# Ethernet_Interface.net
KiCad netlist of a schematic drawn in Altium Designer
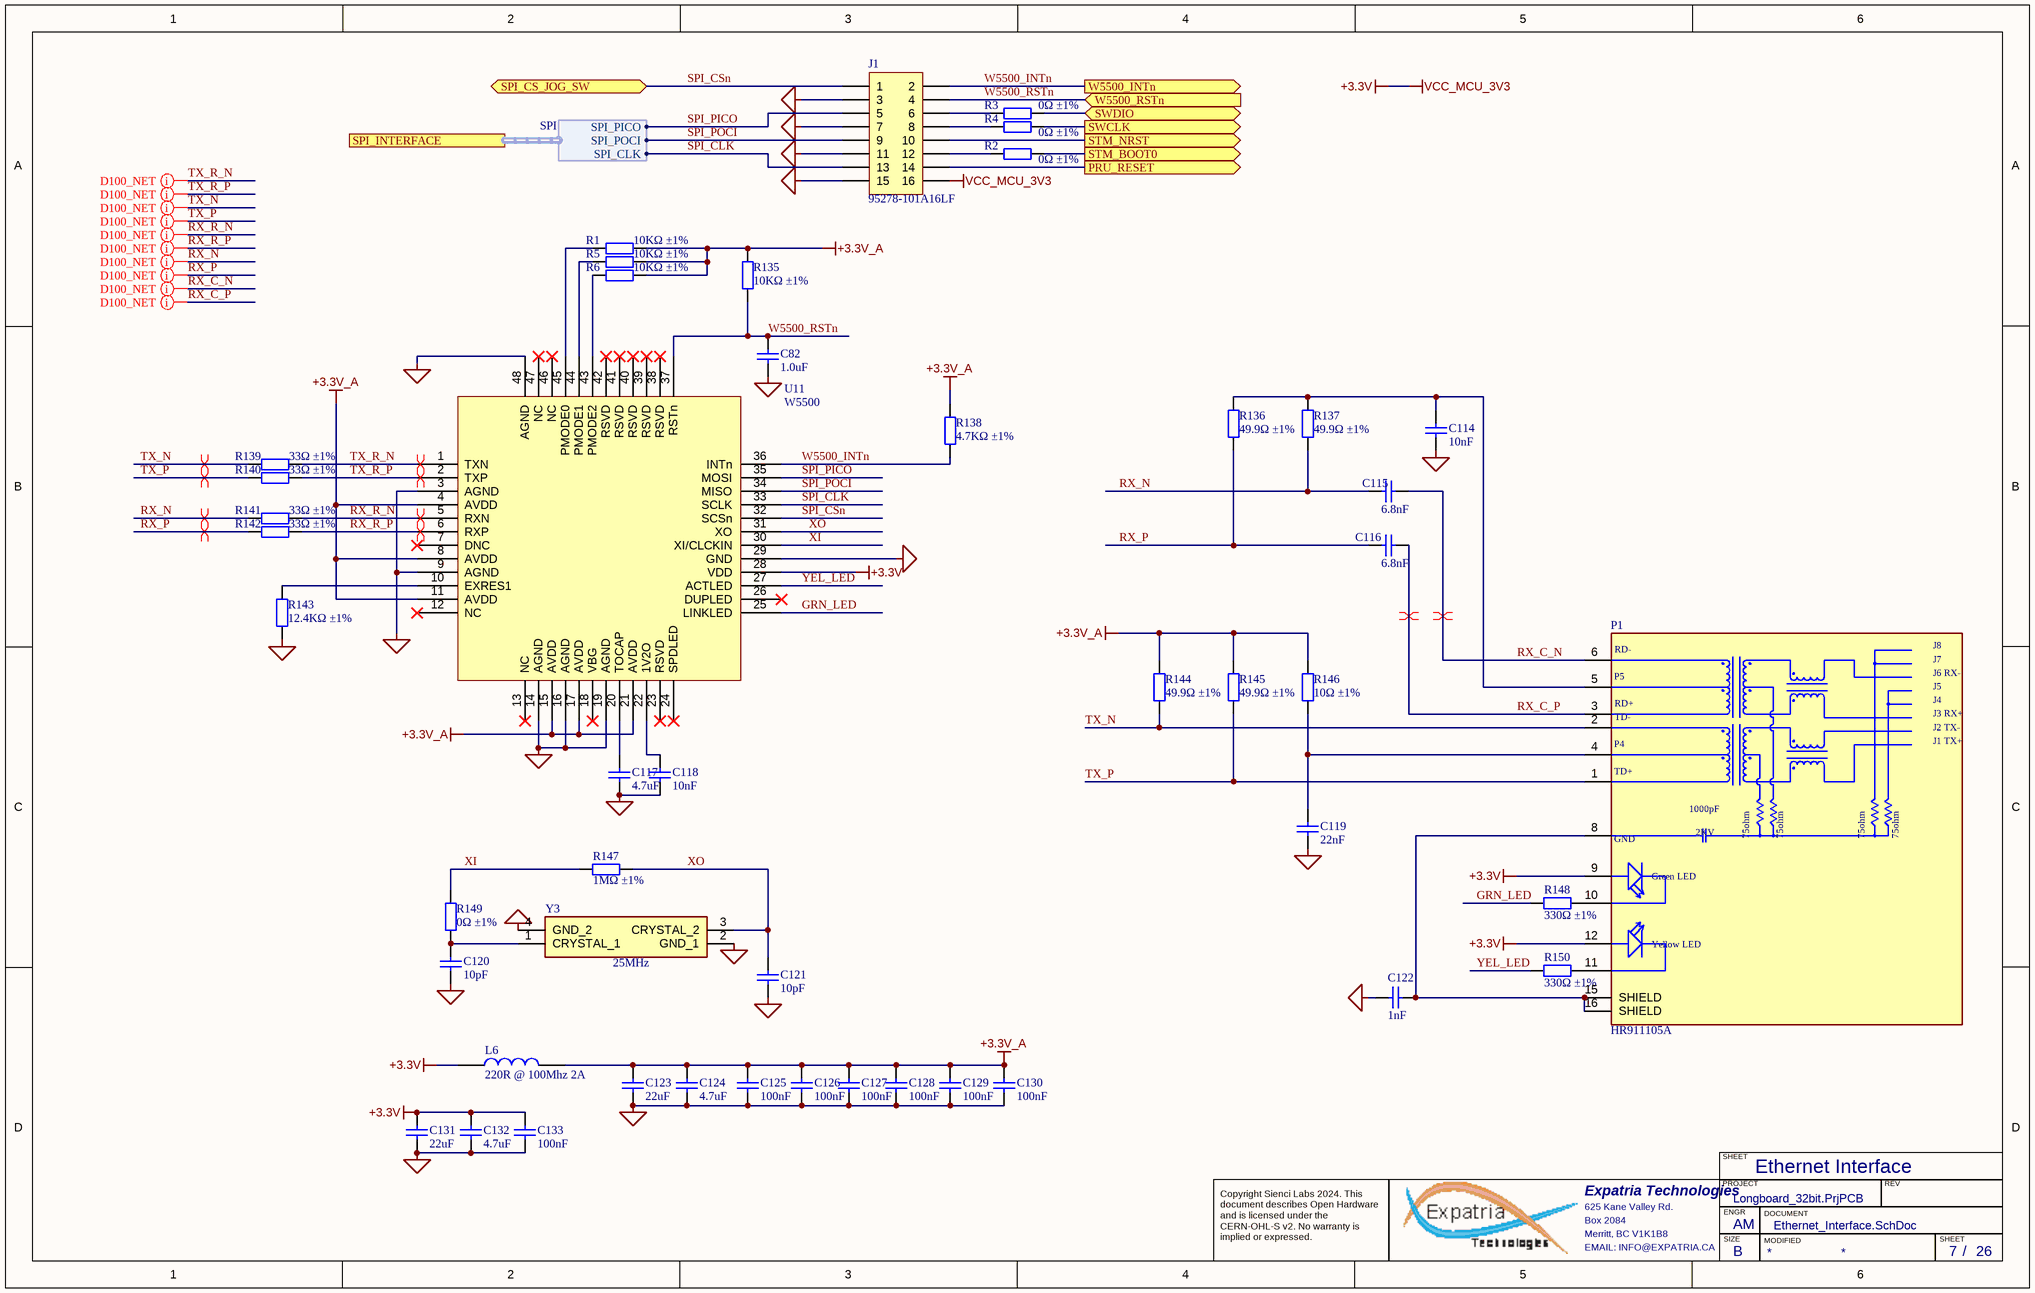
[diagram p0: Ethernet_Interface.SchDoc]

(export (version "E")
  (design (tool "Eeschema 10.0.6"))
  (components
    (comp (ref "C82")
      (value "1.0uF")
      (footprint "0402_C")
      (description "Chip capacitor")
      (fields (field (name "MANUFACTURER") "Samsung Electro-Mechanics") (field (name "TOLERANCE") "10%"))
      (libsource (lib "Cap") (part "0402 1.0uF (105) 10% 25V"))
    )
    (comp (ref "C114")
      (value "10nF")
      (footprint "0402_C")
      (description "Chip capacitors")
      (fields
        (field (name "MANUFACTURER") "Samsung Electro-Mechanics")
        (field (name "MANUFACTURER PART NUMBER") "CL05B103KB5NNNC")
      )
      (libsource (lib "Cap") (part "0402 10nF (103) 10% 50V"))
    )
    (comp (ref "C115")
      (value "6.8nF")
      (footprint "0402_C")
      (description "Chip capacitors")
      (fields
        (field (name "MANUFACTURER") "Guangdong Fenghua Advanced Tech")
        (field (name "MANUFACTURER PART NUMBER") "0402B682K500NT")
      )
      (libsource (lib "Cap") (part "0402 6.8nF (682) 10% 50V"))
    )
    (comp (ref "C116")
      (value "6.8nF")
      (footprint "0402_C")
      (description "Chip capacitors")
      (fields
        (field (name "MANUFACTURER") "Guangdong Fenghua Advanced Tech")
        (field (name "MANUFACTURER PART NUMBER") "0402B682K500NT")
      )
      (libsource (lib "Cap") (part "0402 6.8nF (682) 10% 50V"))
    )
    (comp (ref "C117")
      (value "4.7uF")
      (footprint "0402_C")
      (description "Chip capacitor")
      (fields
        (field (name "MANUFACTURER") "Samsung Electro-Mechanics")
        (field (name "MANUFACTURER PART NUMBER") "CL05A475MP5NRNC")
      )
      (libsource (lib "Cap") (part "0402 4.7uF (475) 20% 10V"))
    )
    (comp (ref "C118")
      (value "10nF")
      (footprint "0402_C")
      (description "Chip capacitors")
      (fields
        (field (name "MANUFACTURER") "Samsung Electro-Mechanics")
        (field (name "MANUFACTURER PART NUMBER") "CL05B103KB5NNNC")
      )
      (libsource (lib "Cap") (part "0402 10nF (103) 10% 50V"))
    )
    (comp (ref "C119")
      (value "22nF")
      (footprint "0402_C")
      (description "Chip capacitors")
      (fields
        (field (name "MANUFACTURER") "Guangdong Fenghua Advanced Tech")
        (field (name "MANUFACTURER PART NUMBER") "0402B223K500NT")
      )
      (libsource (lib "Cap") (part "0402 22nF (223) 10% 50V"))
    )
    (comp (ref "C120")
      (value "10pF")
      (footprint "0402_C")
      (description "Chip capacitors")
      (fields
        (field (name "MANUFACTURER") "Samsung Electro-Mechanics")
        (field (name "MANUFACTURER PART NUMBER") "CL05C100JB5NNNC")
      )
      (libsource (lib "Cap") (part "0402 10pF (100) 5% 50V"))
    )
    (comp (ref "C121")
      (value "10pF")
      (footprint "0402_C")
      (description "Chip capacitors")
      (fields
        (field (name "MANUFACTURER") "Samsung Electro-Mechanics")
        (field (name "MANUFACTURER PART NUMBER") "CL05C100JB5NNNC")
      )
      (libsource (lib "Cap") (part "0402 10pF (100) 5% 50V"))
    )
    (comp (ref "C122")
      (value "1nF")
      (footprint "1206_C")
      (description "Chip capacitors")
      (fields
        (field (name "MANUFACTURER") "Samsung Electro-Mechanics")
        (field (name "MANUFACTURER PART NUMBER") "CL31B102KGFNNNE")
      )
      (libsource (lib "Cap") (part "1206 1nF (102) 10% 500V"))
    )
    (comp (ref "C123")
      (value "22uF")
      (footprint "0805_C")
      (description "25V 22uF X5R ±20% 0805 Multilayer Ceramic Capacitors MLCC - SMD/SMT ROHS")
      (fields (field (name "MANUFACTURER") "Samsung Electro-Mechanics") (field (name "TOLERANCE") "20%"))
      (libsource (lib "Sienci_Labs") (part "0805 22uF (226) 20% 25V"))
    )
    (comp (ref "C124")
      (value "4.7uF")
      (footprint "0603_C")
      (description "16V 4.7uF X5R ±10% 0603 Multilayer Ceramic Capacitors MLCC - SMD/SMT ROHS")
      (fields (field (name "MANUFACTURER") "Samsung Electro-Mechanics") (field (name "TOLERANCE") "10%"))
      (libsource (lib "Sienci_Labs") (part "0603 4.7uF (475) 10% 16V"))
    )
    (comp (ref "C125")
      (value "100nF")
      (footprint "0402_C")
      (description "16V 100nF X7R ±10% 0402 Multilayer Ceramic Capacitors MLCC - SMD/SMT ROHS")
      (fields (field (name "MANUFACTURER") "Samsung Electro-Mechanics") (field (name "TOLERANCE") "10%"))
      (libsource (lib "Sienci_Labs") (part "0402 100nF (104) 10% 16V"))
    )
    (comp (ref "C126")
      (value "100nF")
      (footprint "0402_C")
      (description "16V 100nF X7R ±10% 0402 Multilayer Ceramic Capacitors MLCC - SMD/SMT ROHS")
      (fields (field (name "MANUFACTURER") "Samsung Electro-Mechanics") (field (name "TOLERANCE") "10%"))
      (libsource (lib "Sienci_Labs") (part "0402 100nF (104) 10% 16V"))
    )
    (comp (ref "C127")
      (value "100nF")
      (footprint "0402_C")
      (description "16V 100nF X7R ±10% 0402 Multilayer Ceramic Capacitors MLCC - SMD/SMT ROHS")
      (fields (field (name "MANUFACTURER") "Samsung Electro-Mechanics") (field (name "TOLERANCE") "10%"))
      (libsource (lib "Sienci_Labs") (part "0402 100nF (104) 10% 16V"))
    )
    (comp (ref "C128")
      (value "100nF")
      (footprint "0402_C")
      (description "16V 100nF X7R ±10% 0402 Multilayer Ceramic Capacitors MLCC - SMD/SMT ROHS")
      (fields (field (name "MANUFACTURER") "Samsung Electro-Mechanics") (field (name "TOLERANCE") "10%"))
      (libsource (lib "Sienci_Labs") (part "0402 100nF (104) 10% 16V"))
    )
    (comp (ref "C129")
      (value "100nF")
      (footprint "0402_C")
      (description "16V 100nF X7R ±10% 0402 Multilayer Ceramic Capacitors MLCC - SMD/SMT ROHS")
      (fields (field (name "MANUFACTURER") "Samsung Electro-Mechanics") (field (name "TOLERANCE") "10%"))
      (libsource (lib "Sienci_Labs") (part "0402 100nF (104) 10% 16V"))
    )
    (comp (ref "C130")
      (value "100nF")
      (footprint "0402_C")
      (description "16V 100nF X7R ±10% 0402 Multilayer Ceramic Capacitors MLCC - SMD/SMT ROHS")
      (fields (field (name "MANUFACTURER") "Samsung Electro-Mechanics") (field (name "TOLERANCE") "10%"))
      (libsource (lib "Sienci_Labs") (part "0402 100nF (104) 10% 16V"))
    )
    (comp (ref "C131")
      (value "22uF")
      (footprint "0805_C")
      (description "25V 22uF X5R ±20% 0805 Multilayer Ceramic Capacitors MLCC - SMD/SMT ROHS")
      (fields (field (name "MANUFACTURER") "Samsung Electro-Mechanics") (field (name "TOLERANCE") "20%"))
      (libsource (lib "Sienci_Labs") (part "0805 22uF (226) 20% 25V"))
    )
    (comp (ref "C132")
      (value "4.7uF")
      (footprint "0603_C")
      (description "16V 4.7uF X5R ±10% 0603 Multilayer Ceramic Capacitors MLCC - SMD/SMT ROHS")
      (fields (field (name "MANUFACTURER") "Samsung Electro-Mechanics") (field (name "TOLERANCE") "10%"))
      (libsource (lib "Sienci_Labs") (part "0603 4.7uF (475) 10% 16V"))
    )
    (comp (ref "C133")
      (value "100nF")
      (footprint "0402_C")
      (description "16V 100nF X7R ±10% 0402 Multilayer Ceramic Capacitors MLCC - SMD/SMT ROHS")
      (fields (field (name "MANUFACTURER") "Samsung Electro-Mechanics") (field (name "TOLERANCE") "10%"))
      (libsource (lib "Sienci_Labs") (part "0402 100nF (104) 10% 16V"))
    )
    (comp (ref "J1")
      (value "95278-101A16LF")
      (footprint "95278101A16LF")
      (description "Conn Unshrouded Header HDR 16 POS 2.54mm Solder ST Top Entry SMD BergStik® T/R")
      (fields (field (name "MANUFACTURER") "Amphenol ICC / FCI"))
      (libsource (lib "Sienci_Labs") (part "95278-101A16LF"))
    )
    (comp (ref "L6")
      (value "220R @ 100Mhz 2A")
      (footprint "0805_R")
      (description "150mΩ ±25% 220Ω@100MHz 0805 Ferrite Beads ROHS")
      (fields
        (field (name "MANUFACTURER PART NUMBER") "CBW201209U221T")
        (field (name "MANUFACTURER") "FH (Guangdong Fenghua Advanced Tech)")
      )
      (libsource (lib "Sienci_Labs") (part "CBW201209U221T"))
    )
    (comp (ref "P1")
      (value "HR911105A")
      (footprint "HANRUN_HR911105A")
      (description "HR911105A Ethernet Interface Arduino Platform Evaluation Expansion Board")
      (fields (field (name "MANUFACTURER") "DFRobot"))
      (libsource (lib "Sienci_Labs") (part "HR911105A"))
    )
    (comp (ref "R1")
      (value "10KΩ ±1%")
      (footprint "0402_R")
      (description "Chip resistor")
      (fields
        (field (name "MANUFACTURER") "Uniroyal Elec")
        (field (name "MANUFACTURER PART NUMBER") "0402WGF1002TCE")
      )
      (libsource (lib "RES") (part "0402 10K (1002) 1%"))
    )
    (comp (ref "R2")
      (value "0Ω ±1%")
      (footprint "0603_R")
      (description "Chip resistor")
      (fields
        (field (name "MANUFACTURER") "Uniroyal Elec")
        (field (name "MANUFACTURER PART NUMBER") "0603WAF0000T5E")
      )
      (libsource (lib "RES") (part "0603 0R (0R0) 1%"))
    )
    (comp (ref "R3")
      (value "0Ω ±1%")
      (footprint "0603_R")
      (description "Chip resistor")
      (fields
        (field (name "MANUFACTURER") "Uniroyal Elec")
        (field (name "MANUFACTURER PART NUMBER") "0603WAF0000T5E")
      )
      (libsource (lib "RES") (part "0603 0R (0R0) 1%"))
    )
    (comp (ref "R4")
      (value "0Ω ±1%")
      (footprint "0603_R")
      (description "Chip resistor")
      (fields
        (field (name "MANUFACTURER") "Uniroyal Elec")
        (field (name "MANUFACTURER PART NUMBER") "0603WAF0000T5E")
      )
      (libsource (lib "RES") (part "0603 0R (0R0) 1%"))
    )
    (comp (ref "R5")
      (value "10KΩ ±1%")
      (footprint "0402_R")
      (description "Chip resistor")
      (fields
        (field (name "MANUFACTURER") "Uniroyal Elec")
        (field (name "MANUFACTURER PART NUMBER") "0402WGF1002TCE")
      )
      (libsource (lib "RES") (part "0402 10K (1002) 1%"))
    )
    (comp (ref "R6")
      (value "10KΩ ±1%")
      (footprint "0402_R")
      (description "Chip resistor")
      (fields
        (field (name "MANUFACTURER") "Uniroyal Elec")
        (field (name "MANUFACTURER PART NUMBER") "0402WGF1002TCE")
      )
      (libsource (lib "RES") (part "0402 10K (1002) 1%"))
    )
    (comp (ref "R135")
      (value "10KΩ ±1%")
      (footprint "0402_R")
      (description "Chip resistor")
      (fields
        (field (name "MANUFACTURER") "Uniroyal Elec")
        (field (name "MANUFACTURER PART NUMBER") "0402WGF1002TCE")
      )
      (libsource (lib "") (part "0402 10K (1002) 1%_1"))
    )
    (comp (ref "R136")
      (value "49.9Ω ±1%")
      (footprint "0402_R")
      (description "Chip resistor")
      (fields
        (field (name "MANUFACTURER") "Uniroyal Elec")
        (field (name "MANUFACTURER PART NUMBER") "0402WGF499JTCE")
      )
      (libsource (lib "RES") (part "0402 49.9R (49R9) 1%"))
    )
    (comp (ref "R137")
      (value "49.9Ω ±1%")
      (footprint "0402_R")
      (description "Chip resistor")
      (fields
        (field (name "MANUFACTURER") "Uniroyal Elec")
        (field (name "MANUFACTURER PART NUMBER") "0402WGF499JTCE")
      )
      (libsource (lib "RES") (part "0402 49.9R (49R9) 1%"))
    )
    (comp (ref "R138")
      (value "4.7KΩ ±1%")
      (footprint "0402_R")
      (description "Chip resistor")
      (fields
        (field (name "MANUFACTURER") "Uniroyal Elec")
        (field (name "MANUFACTURER PART NUMBER") "0402WGF4701TCE")
      )
      (libsource (lib "RES") (part "0402 4.7K (4701) 1%"))
    )
    (comp (ref "R139")
      (value "33Ω ±1%")
      (footprint "0402_R")
      (description "Chip resistor")
      (fields
        (field (name "MANUFACTURER") "Uniroyal Elec")
        (field (name "MANUFACTURER PART NUMBER") "0402WGF330JTCE")
      )
      (libsource (lib "RES") (part "0402 33R (33R0) 1%"))
    )
    (comp (ref "R140")
      (value "33Ω ±1%")
      (footprint "0402_R")
      (description "Chip resistor")
      (fields
        (field (name "MANUFACTURER") "Uniroyal Elec")
        (field (name "MANUFACTURER PART NUMBER") "0402WGF330JTCE")
      )
      (libsource (lib "RES") (part "0402 33R (33R0) 1%"))
    )
    (comp (ref "R141")
      (value "33Ω ±1%")
      (footprint "0402_R")
      (description "Chip resistor")
      (fields
        (field (name "MANUFACTURER") "Uniroyal Elec")
        (field (name "MANUFACTURER PART NUMBER") "0402WGF330JTCE")
      )
      (libsource (lib "RES") (part "0402 33R (33R0) 1%"))
    )
    (comp (ref "R142")
      (value "33Ω ±1%")
      (footprint "0402_R")
      (description "Chip resistor")
      (fields
        (field (name "MANUFACTURER") "Uniroyal Elec")
        (field (name "MANUFACTURER PART NUMBER") "0402WGF330JTCE")
      )
      (libsource (lib "RES") (part "0402 33R (33R0) 1%"))
    )
    (comp (ref "R143")
      (value "12.4KΩ ±1%")
      (footprint "0603_R")
      (description "Chip resistor")
      (fields
        (field (name "MANUFACTURER") "Uniroyal Elec")
        (field (name "MANUFACTURER PART NUMBER") "0603WAF1242T5E")
      )
      (libsource (lib "RES") (part "0603 10K (1002) 1%"))
    )
    (comp (ref "R144")
      (value "49.9Ω ±1%")
      (footprint "0402_R")
      (description "Chip resistor")
      (fields
        (field (name "MANUFACTURER") "Uniroyal Elec")
        (field (name "MANUFACTURER PART NUMBER") "0402WGF499JTCE")
      )
      (libsource (lib "RES") (part "0402 49.9R (49R9) 1%"))
    )
    (comp (ref "R145")
      (value "49.9Ω ±1%")
      (footprint "0402_R")
      (description "Chip resistor")
      (fields
        (field (name "MANUFACTURER") "Uniroyal Elec")
        (field (name "MANUFACTURER PART NUMBER") "0402WGF499JTCE")
      )
      (libsource (lib "RES") (part "0402 49.9R (49R9) 1%"))
    )
    (comp (ref "R146")
      (value "10Ω ±1%")
      (footprint "0402_R")
      (description "Chip resistor")
      (fields
        (field (name "MANUFACTURER") "Uniroyal Elec")
        (field (name "MANUFACTURER PART NUMBER") "0402WGF100JTCE")
      )
      (libsource (lib "RES") (part "0402 10R (10R0) 1%"))
    )
    (comp (ref "R147")
      (value "1MΩ ±1%")
      (footprint "0402_R")
      (description "Chip resistor")
      (fields
        (field (name "MANUFACTURER") "Uniroyal Elec")
        (field (name "MANUFACTURER PART NUMBER") "0402WGF1004TCE")
      )
      (libsource (lib "RES") (part "0402 1M (1004) 1%"))
    )
    (comp (ref "R148")
      (value "330Ω ±1%")
      (footprint "0402_R")
      (description "Chip resistor")
      (fields
        (field (name "MANUFACTURER") "Uniroyal Elec")
        (field (name "MANUFACTURER PART NUMBER") "0402WGF3300TCE")
      )
      (libsource (lib "RES") (part "0402 330R (3300) 1%"))
    )
    (comp (ref "R149")
      (value "0Ω ±1%")
      (footprint "0402_R")
      (description "Chip resistor")
      (fields
        (field (name "MANUFACTURER") "Uniroyal Elec")
        (field (name "MANUFACTURER PART NUMBER") "0402WGF0000TCE")
      )
      (libsource (lib "RES") (part "0402 0R (0R0) 1%"))
    )
    (comp (ref "R150")
      (value "330Ω ±1%")
      (footprint "0402_R")
      (description "Chip resistor")
      (fields
        (field (name "MANUFACTURER") "Uniroyal Elec")
        (field (name "MANUFACTURER PART NUMBER") "0402WGF3300TCE")
      )
      (libsource (lib "RES") (part "0402 330R (3300) 1%"))
    )
    (comp (ref "U11")
      (value "W5500")
      (footprint "LQFP-48_7x7x05P")
      (description "Ethernet Controllers 2.97V ~ 3.63V 10/100 Base-T/TX PHY SPI LQFP-48_7x7x05P Ethernet ICs ROHS")
      (fields (field (name "MANUFACTURER") "WIZNET"))
      (libsource (lib "Sienci_Labs") (part "W5500_[C32843]"))
    )
    (comp (ref "Y3")
      (value "25MHz")
      (footprint "YSX321SL")
      (description "25MHz SMD Crystal Resonator 20pF ±10ppm ±30ppm -40℃~+85℃ SMD3225-4P Crystals ROHS")
      (fields
        (field (name "MANUFACTURER") "Yangxing Tech")
        (field (name "MANUFACTURER PART NUMBER") "X322525MSB4SI")
      )
      (libsource (lib "Sienci_Labs") (part "X322525MSB4SI"))
    )
  )
  (nets
    (net (code "2") (name "+3.3V") (class "Default")
      (node (ref "C131") (pin "2") (pinfunction "2_2") (pintype "passive"))
      (node (ref "C132") (pin "2") (pinfunction "2_2") (pintype "passive"))
      (node (ref "C133") (pin "2") (pinfunction "2_2") (pintype "passive"))
      (node (ref "J1") (pin "16") (pinfunction "16_16") (pintype "passive"))
      (node (ref "L6") (pin "1") (pinfunction "1_1") (pintype "passive"))
      (node (ref "P1") (pin "12") (pinfunction "YA_12") (pintype "passive"))
      (node (ref "P1") (pin "9") (pinfunction "GA_9") (pintype "passive"))
      (node (ref "U11") (pin "28") (pinfunction "VDD_28") (pintype "passive"))
    )
    (net (code "3") (name "+3.3V_A") (class "Default")
      (node (ref "C123") (pin "2") (pinfunction "2_2") (pintype "passive"))
      (node (ref "C124") (pin "2") (pinfunction "2_2") (pintype "passive"))
      (node (ref "C125") (pin "2") (pinfunction "2_2") (pintype "passive"))
      (node (ref "C126") (pin "2") (pinfunction "2_2") (pintype "passive"))
      (node (ref "C127") (pin "2") (pinfunction "2_2") (pintype "passive"))
      (node (ref "C128") (pin "2") (pinfunction "2_2") (pintype "passive"))
      (node (ref "C129") (pin "2") (pinfunction "2_2") (pintype "passive"))
      (node (ref "C130") (pin "2") (pinfunction "2_2") (pintype "passive"))
      (node (ref "L6") (pin "2") (pinfunction "2_2") (pintype "passive"))
      (node (ref "R1") (pin "1") (pinfunction "1_1") (pintype "passive"))
      (node (ref "R135") (pin "1") (pinfunction "1_1") (pintype "passive"))
      (node (ref "R138") (pin "1") (pinfunction "1_1") (pintype "passive"))
      (node (ref "R144") (pin "1") (pinfunction "1_1") (pintype "passive"))
      (node (ref "R145") (pin "1") (pinfunction "1_1") (pintype "passive"))
      (node (ref "R146") (pin "1") (pinfunction "1_1") (pintype "passive"))
      (node (ref "R5") (pin "1") (pinfunction "1_1") (pintype "passive"))
      (node (ref "R6") (pin "1") (pinfunction "1_1") (pintype "passive"))
      (node (ref "U11") (pin "11") (pinfunction "AVDD_11") (pintype "passive"))
      (node (ref "U11") (pin "15") (pinfunction "AVDD_15") (pintype "passive"))
      (node (ref "U11") (pin "17") (pinfunction "AVDD_17") (pintype "passive"))
      (node (ref "U11") (pin "21") (pinfunction "AVDD_21") (pintype "passive"))
      (node (ref "U11") (pin "4") (pinfunction "AVDD_4") (pintype "passive"))
      (node (ref "U11") (pin "8") (pinfunction "AVDD_8") (pintype "passive"))
    )
    (net (code "4") (name "/GRN_LED") (class "Default")
      (node (ref "R148") (pin "1") (pinfunction "1_1") (pintype "passive"))
      (node (ref "U11") (pin "25") (pinfunction "LINKLED_25") (pintype "passive"))
    )
    (net (code "5") (name "/PRU_RESET") (class "Default")
      (node (ref "J1") (pin "14") (pinfunction "14_14") (pintype "passive"))
    )
    (net (code "6") (name "/RX_C_N") (class "Default")
      (node (ref "C115") (pin "1") (pinfunction "1_1") (pintype "passive"))
      (node (ref "P1") (pin "6") (pinfunction "RD-_6") (pintype "passive"))
    )
    (net (code "7") (name "/RX_C_P") (class "Default")
      (node (ref "C116") (pin "1") (pinfunction "1_1") (pintype "passive"))
      (node (ref "P1") (pin "3") (pinfunction "RD+_3") (pintype "passive"))
    )
    (net (code "8") (name "/RX_N") (class "Default")
      (node (ref "C115") (pin "2") (pinfunction "2_2") (pintype "passive"))
      (node (ref "R137") (pin "2") (pinfunction "2_2") (pintype "passive"))
      (node (ref "R141") (pin "1") (pinfunction "1_1") (pintype "passive"))
    )
    (net (code "9") (name "/RX_P") (class "Default")
      (node (ref "C116") (pin "2") (pinfunction "2_2") (pintype "passive"))
      (node (ref "R136") (pin "2") (pinfunction "2_2") (pintype "passive"))
      (node (ref "R142") (pin "1") (pinfunction "1_1") (pintype "passive"))
    )
    (net (code "10") (name "/RX_R_N") (class "Default")
      (node (ref "R141") (pin "2") (pinfunction "2_2") (pintype "passive"))
      (node (ref "U11") (pin "5") (pinfunction "RXN_5") (pintype "passive"))
    )
    (net (code "11") (name "/RX_R_P") (class "Default")
      (node (ref "R142") (pin "2") (pinfunction "2_2") (pintype "passive"))
      (node (ref "U11") (pin "6") (pinfunction "RXP_6") (pintype "passive"))
    )
    (net (code "12") (name "/SPI_CLK") (class "Default")
      (node (ref "J1") (pin "13") (pinfunction "13_13") (pintype "passive"))
      (node (ref "U11") (pin "33") (pinfunction "SCLK_33") (pintype "passive"))
    )
    (net (code "13") (name "/SPI_CSn") (class "Default")
      (node (ref "J1") (pin "1") (pinfunction "1_1") (pintype "passive"))
      (node (ref "U11") (pin "32") (pinfunction "SCSn_32") (pintype "passive"))
    )
    (net (code "14") (name "/SPI_PICO") (class "Default")
      (node (ref "J1") (pin "5") (pinfunction "5_5") (pintype "passive"))
      (node (ref "U11") (pin "35") (pinfunction "MOSI_35") (pintype "passive"))
    )
    (net (code "15") (name "/SPI_POCI") (class "Default")
      (node (ref "J1") (pin "9") (pinfunction "9_9") (pintype "passive"))
      (node (ref "U11") (pin "34") (pinfunction "MISO_34") (pintype "passive"))
    )
    (net (code "16") (name "/STM_BOOT0") (class "Default")
      (node (ref "R2") (pin "1") (pinfunction "1_1") (pintype "passive"))
    )
    (net (code "17") (name "/STM_NRST") (class "Default")
      (node (ref "J1") (pin "10") (pinfunction "10_10") (pintype "passive"))
    )
    (net (code "18") (name "/SWCLK") (class "Default")
      (node (ref "R4") (pin "1") (pinfunction "1_1") (pintype "passive"))
    )
    (net (code "19") (name "/SWDIO") (class "Default")
      (node (ref "R3") (pin "1") (pinfunction "1_1") (pintype "passive"))
    )
    (net (code "20") (name "/TX_N") (class "Default")
      (node (ref "P1") (pin "2") (pinfunction "TD-_2") (pintype "passive"))
      (node (ref "R139") (pin "1") (pinfunction "1_1") (pintype "passive"))
      (node (ref "R144") (pin "2") (pinfunction "2_2") (pintype "passive"))
    )
    (net (code "21") (name "/TX_P") (class "Default")
      (node (ref "P1") (pin "1") (pinfunction "TD+_1") (pintype "passive"))
      (node (ref "R140") (pin "1") (pinfunction "1_1") (pintype "passive"))
      (node (ref "R145") (pin "2") (pinfunction "2_2") (pintype "passive"))
    )
    (net (code "22") (name "/TX_R_N") (class "Default")
      (node (ref "R139") (pin "2") (pinfunction "2_2") (pintype "passive"))
      (node (ref "U11") (pin "1") (pinfunction "TXN_1") (pintype "passive"))
    )
    (net (code "23") (name "/TX_R_P") (class "Default")
      (node (ref "R140") (pin "2") (pinfunction "2_2") (pintype "passive"))
      (node (ref "U11") (pin "2") (pinfunction "TXP_2") (pintype "passive"))
    )
    (net (code "24") (name "/W5500_INTn") (class "Default")
      (node (ref "J1") (pin "2") (pinfunction "2_2") (pintype "passive"))
      (node (ref "R138") (pin "2") (pinfunction "2_2") (pintype "passive"))
      (node (ref "U11") (pin "36") (pinfunction "INTn_36") (pintype "passive"))
    )
    (net (code "25") (name "/W5500_RSTn") (class "Default")
      (node (ref "C82") (pin "2") (pinfunction "2_2") (pintype "passive"))
      (node (ref "J1") (pin "4") (pinfunction "4_4") (pintype "passive"))
      (node (ref "R135") (pin "2") (pinfunction "2_2") (pintype "passive"))
      (node (ref "U11") (pin "37") (pinfunction "RSTn_37") (pintype "passive"))
    )
    (net (code "26") (name "/XI") (class "Default")
      (node (ref "R147") (pin "1") (pinfunction "1_1") (pintype "passive"))
      (node (ref "R149") (pin "1") (pinfunction "1_1") (pintype "passive"))
      (node (ref "U11") (pin "30") (pinfunction "XI/CLCKIN_30") (pintype "passive"))
    )
    (net (code "27") (name "/XO") (class "Default")
      (node (ref "C121") (pin "2") (pinfunction "2_2") (pintype "passive"))
      (node (ref "R147") (pin "2") (pinfunction "2_2") (pintype "passive"))
      (node (ref "U11") (pin "31") (pinfunction "XO_31") (pintype "passive"))
      (node (ref "Y3") (pin "3") (pinfunction "CRYSTAL_2_3") (pintype "passive"))
    )
    (net (code "28") (name "/YEL_LED") (class "Default")
      (node (ref "R150") (pin "1") (pinfunction "1_1") (pintype "passive"))
      (node (ref "U11") (pin "27") (pinfunction "ACTLED_27") (pintype "passive"))
    )
    (net (code "30") (name "MCU_GND") (class "Default")
      (node (ref "C114") (pin "1") (pinfunction "1_1") (pintype "passive"))
      (node (ref "C117") (pin "1") (pinfunction "1_1") (pintype "passive"))
      (node (ref "C118") (pin "1") (pinfunction "1_1") (pintype "passive"))
      (node (ref "C119") (pin "1") (pinfunction "1_1") (pintype "passive"))
      (node (ref "C120") (pin "1") (pinfunction "1_1") (pintype "passive"))
      (node (ref "C121") (pin "1") (pinfunction "1_1") (pintype "passive"))
      (node (ref "C122") (pin "1") (pinfunction "1_1") (pintype "passive"))
      (node (ref "C123") (pin "1") (pinfunction "1_1") (pintype "passive"))
      (node (ref "C124") (pin "1") (pinfunction "1_1") (pintype "passive"))
      (node (ref "C125") (pin "1") (pinfunction "1_1") (pintype "passive"))
      (node (ref "C126") (pin "1") (pinfunction "1_1") (pintype "passive"))
      (node (ref "C127") (pin "1") (pinfunction "1_1") (pintype "passive"))
      (node (ref "C128") (pin "1") (pinfunction "1_1") (pintype "passive"))
      (node (ref "C129") (pin "1") (pinfunction "1_1") (pintype "passive"))
      (node (ref "C130") (pin "1") (pinfunction "1_1") (pintype "passive"))
      (node (ref "C131") (pin "1") (pinfunction "1_1") (pintype "passive"))
      (node (ref "C132") (pin "1") (pinfunction "1_1") (pintype "passive"))
      (node (ref "C133") (pin "1") (pinfunction "1_1") (pintype "passive"))
      (node (ref "C82") (pin "1") (pinfunction "1_1") (pintype "passive"))
      (node (ref "J1") (pin "11") (pinfunction "11_11") (pintype "passive"))
      (node (ref "J1") (pin "15") (pinfunction "15_15") (pintype "passive"))
      (node (ref "J1") (pin "3") (pinfunction "3_3") (pintype "passive"))
      (node (ref "J1") (pin "7") (pinfunction "7_7") (pintype "passive"))
      (node (ref "R143") (pin "1") (pinfunction "1_1") (pintype "passive"))
      (node (ref "U11") (pin "14") (pinfunction "AGND_14") (pintype "passive"))
      (node (ref "U11") (pin "16") (pinfunction "AGND_16") (pintype "passive"))
      (node (ref "U11") (pin "19") (pinfunction "AGND_19") (pintype "passive"))
      (node (ref "U11") (pin "29") (pinfunction "GND_29") (pintype "passive"))
      (node (ref "U11") (pin "3") (pinfunction "AGND_3") (pintype "passive"))
      (node (ref "U11") (pin "48") (pinfunction "AGND_48") (pintype "passive"))
      (node (ref "U11") (pin "9") (pinfunction "AGND_9") (pintype "passive"))
      (node (ref "Y3") (pin "2") (pinfunction "GND_1_2") (pintype "passive"))
      (node (ref "Y3") (pin "4") (pinfunction "GND_2_4") (pintype "passive"))
    )
    (net (code "31") (name "Net-(J1-Pad6)") (class "Default")
      (node (ref "J1") (pin "6") (pinfunction "6_6") (pintype "passive"))
      (node (ref "R3") (pin "2") (pinfunction "2_2") (pintype "passive"))
    )
    (net (code "32") (name "Net-(J1-Pad8)") (class "Default")
      (node (ref "J1") (pin "8") (pinfunction "8_8") (pintype "passive"))
      (node (ref "R4") (pin "2") (pinfunction "2_2") (pintype "passive"))
    )
    (net (code "33") (name "Net-(J1-Pad12)") (class "Default")
      (node (ref "J1") (pin "12") (pinfunction "12_12") (pintype "passive"))
      (node (ref "R2") (pin "2") (pinfunction "2_2") (pintype "passive"))
    )
    (net (code "34") (name "Net-(P1-GC)") (class "Default")
      (node (ref "P1") (pin "10") (pinfunction "GC_10") (pintype "passive"))
      (node (ref "R148") (pin "2") (pinfunction "2_2") (pintype "passive"))
    )
    (net (code "35") (name "Net-(P1-GND)") (class "Default")
      (node (ref "C122") (pin "2") (pinfunction "2_2") (pintype "passive"))
      (node (ref "P1") (pin "15") (pinfunction "SHIELD_15") (pintype "passive"))
      (node (ref "P1") (pin "16") (pinfunction "SHIELD_16") (pintype "passive"))
      (node (ref "P1") (pin "8") (pinfunction "GND_8") (pintype "power_in"))
    )
    (net (code "36") (name "Net-(P1-P4)") (class "Default")
      (node (ref "C119") (pin "2") (pinfunction "2_2") (pintype "passive"))
      (node (ref "P1") (pin "4") (pinfunction "P4_4") (pintype "passive"))
      (node (ref "R146") (pin "2") (pinfunction "2_2") (pintype "passive"))
    )
    (net (code "37") (name "Net-(P1-P5)") (class "Default")
      (node (ref "C114") (pin "2") (pinfunction "2_2") (pintype "passive"))
      (node (ref "P1") (pin "5") (pinfunction "P5_5") (pintype "passive"))
      (node (ref "R136") (pin "1") (pinfunction "1_1") (pintype "passive"))
      (node (ref "R137") (pin "1") (pinfunction "1_1") (pintype "passive"))
    )
    (net (code "38") (name "Net-(P1-YC)") (class "Default")
      (node (ref "P1") (pin "11") (pinfunction "YC_11") (pintype "passive"))
      (node (ref "R150") (pin "2") (pinfunction "2_2") (pintype "passive"))
    )
    (net (code "39") (name "Net-(U11-1V2O)") (class "Default")
      (node (ref "C118") (pin "2") (pinfunction "2_2") (pintype "passive"))
      (node (ref "U11") (pin "22") (pinfunction "1V2O_22") (pintype "passive"))
    )
    (net (code "40") (name "Net-(U11-EXRES1)") (class "Default")
      (node (ref "R143") (pin "2") (pinfunction "2_2") (pintype "passive"))
      (node (ref "U11") (pin "10") (pinfunction "EXRES1_10") (pintype "passive"))
    )
    (net (code "41") (name "Net-(U11-PMODE0)") (class "Default")
      (node (ref "R1") (pin "2") (pinfunction "2_2") (pintype "passive"))
      (node (ref "U11") (pin "45") (pinfunction "PMODE0_45") (pintype "passive"))
    )
    (net (code "42") (name "Net-(U11-PMODE1)") (class "Default")
      (node (ref "R5") (pin "2") (pinfunction "2_2") (pintype "passive"))
      (node (ref "U11") (pin "44") (pinfunction "PMODE1_44") (pintype "passive"))
    )
    (net (code "43") (name "Net-(U11-PMODE2)") (class "Default")
      (node (ref "R6") (pin "2") (pinfunction "2_2") (pintype "passive"))
      (node (ref "U11") (pin "43") (pinfunction "PMODE2_43") (pintype "passive"))
    )
    (net (code "44") (name "Net-(U11-TOCAP)") (class "Default")
      (node (ref "C117") (pin "2") (pinfunction "2_2") (pintype "passive"))
      (node (ref "U11") (pin "20") (pinfunction "TOCAP_20") (pintype "passive"))
    )
    (net (code "45") (name "Net-(Y3-CRYSTAL_1)") (class "Default")
      (node (ref "C120") (pin "2") (pinfunction "2_2") (pintype "passive"))
      (node (ref "R149") (pin "2") (pinfunction "2_2") (pintype "passive"))
      (node (ref "Y3") (pin "1") (pinfunction "CRYSTAL_1_1") (pintype "passive"))
    )
    (net (code "46") (name "unconnected-(U11-DNC-Pad7)") (class "Default")
      (node (ref "U11") (pin "7") (pinfunction "DNC_7") (pintype "passive+no_connect"))
    )
    (net (code "47") (name "unconnected-(U11-DUPLED-Pad26)") (class "Default")
      (node (ref "U11") (pin "26") (pinfunction "DUPLED_26") (pintype "passive+no_connect"))
    )
    (net (code "48") (name "unconnected-(U11-NC-Pad12)") (class "Default")
      (node (ref "U11") (pin "12") (pinfunction "NC_12") (pintype "passive+no_connect"))
    )
    (net (code "49") (name "unconnected-(U11-NC-Pad13)") (class "Default")
      (node (ref "U11") (pin "13") (pinfunction "NC_13") (pintype "passive+no_connect"))
    )
    (net (code "50") (name "unconnected-(U11-NC-Pad46)") (class "Default")
      (node (ref "U11") (pin "46") (pinfunction "NC_46") (pintype "passive+no_connect"))
    )
    (net (code "51") (name "unconnected-(U11-NC-Pad47)") (class "Default")
      (node (ref "U11") (pin "47") (pinfunction "NC_47") (pintype "passive+no_connect"))
    )
    (net (code "52") (name "unconnected-(U11-RSVD-Pad23)") (class "Default")
      (node (ref "U11") (pin "23") (pinfunction "RSVD_23") (pintype "passive+no_connect"))
    )
    (net (code "53") (name "unconnected-(U11-RSVD-Pad38)") (class "Default")
      (node (ref "U11") (pin "38") (pinfunction "RSVD_38") (pintype "passive+no_connect"))
    )
    (net (code "54") (name "unconnected-(U11-RSVD-Pad39)") (class "Default")
      (node (ref "U11") (pin "39") (pinfunction "RSVD_39") (pintype "passive+no_connect"))
    )
    (net (code "55") (name "unconnected-(U11-RSVD-Pad40)") (class "Default")
      (node (ref "U11") (pin "40") (pinfunction "RSVD_40") (pintype "passive+no_connect"))
    )
    (net (code "56") (name "unconnected-(U11-RSVD-Pad41)") (class "Default")
      (node (ref "U11") (pin "41") (pinfunction "RSVD_41") (pintype "passive+no_connect"))
    )
    (net (code "57") (name "unconnected-(U11-RSVD-Pad42)") (class "Default")
      (node (ref "U11") (pin "42") (pinfunction "RSVD_42") (pintype "passive+no_connect"))
    )
    (net (code "58") (name "unconnected-(U11-SPDLED-Pad24)") (class "Default")
      (node (ref "U11") (pin "24") (pinfunction "SPDLED_24") (pintype "passive+no_connect"))
    )
    (net (code "59") (name "unconnected-(U11-VBG-Pad18)") (class "Default")
      (node (ref "U11") (pin "18") (pinfunction "VBG_18") (pintype "passive+no_connect"))
    )
  )
)
